# MD.net
KiCad netlist of a schematic drawn in EAGLE
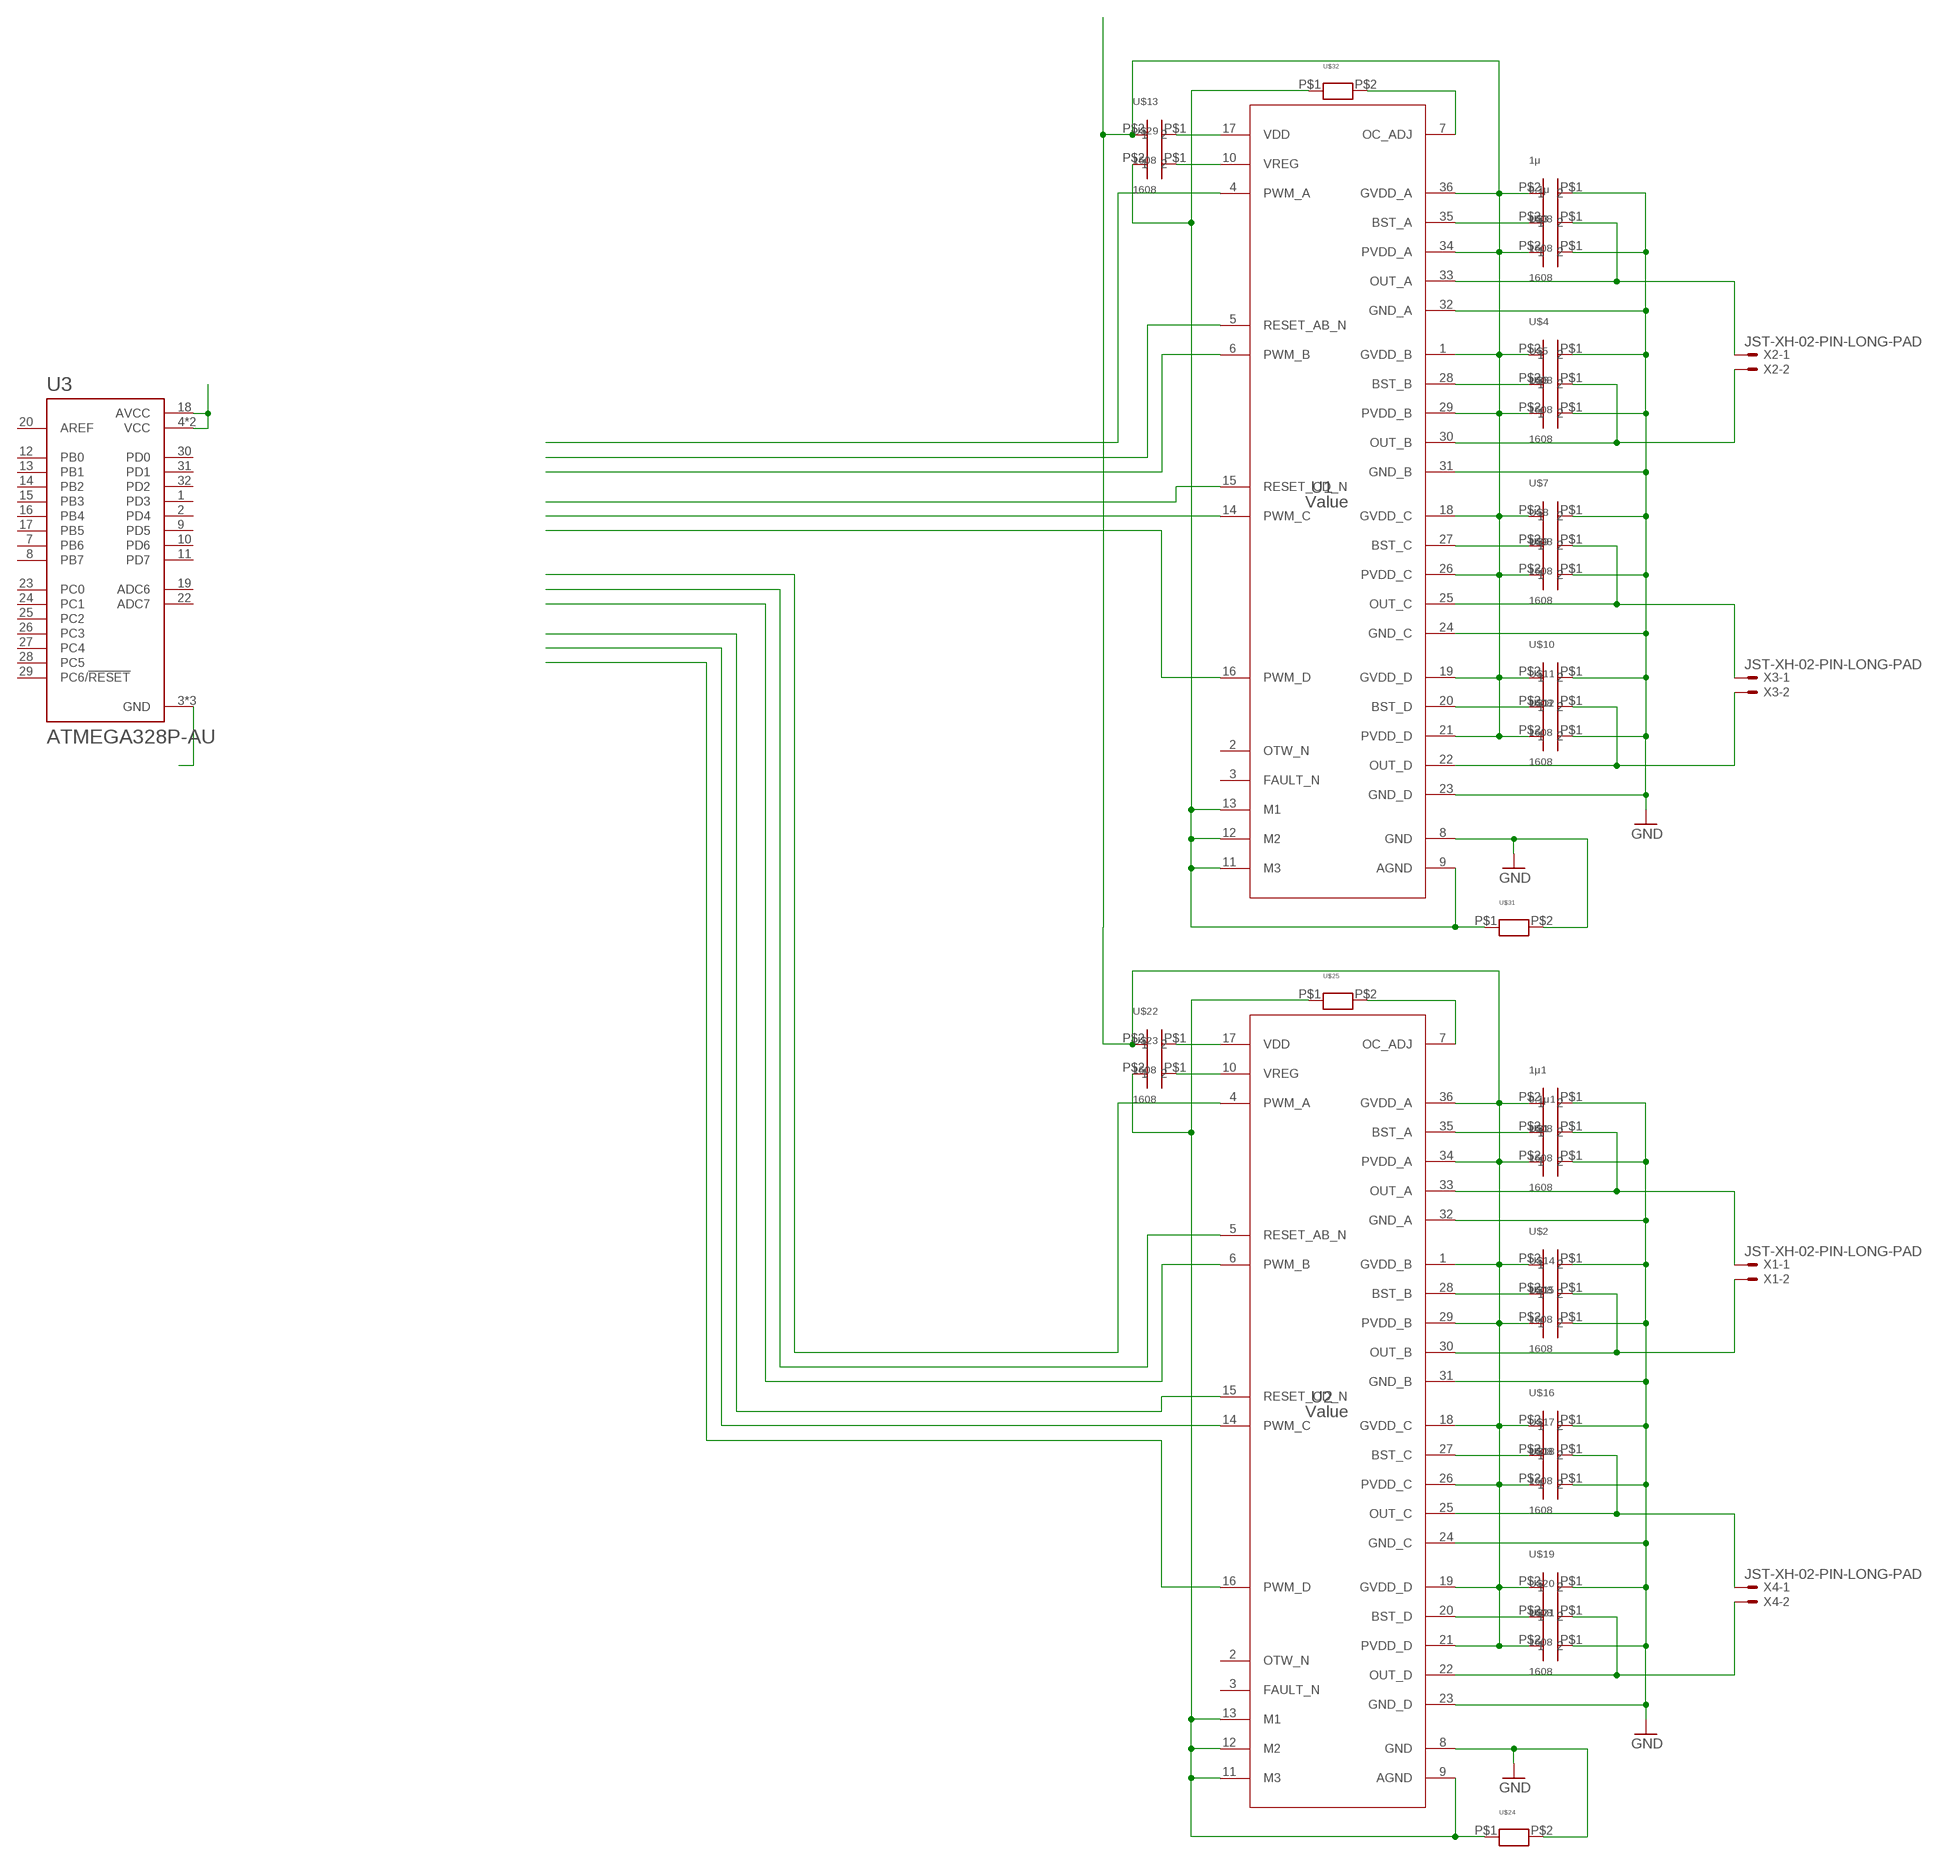
[diagram p0: schematic, sheet 1]

(export (version "E")
  (design (tool "Eeschema 10.0.6"))
  (components
    (comp (ref "0.1μ")
      (value "1608")
      (footprint "eagle-import:CON")
      (libsource (lib "eagle-import") (part "1608"))
    )
    (comp (ref "0.1μ1")
      (value "1608")
      (footprint "eagle-import:CON")
      (libsource (lib "eagle-import") (part "1608"))
    )
    (comp (ref "1μ")
      (value "1608")
      (footprint "eagle-import:CON")
      (libsource (lib "eagle-import") (part "1608"))
    )
    (comp (ref "1μ1")
      (value "1608")
      (footprint "eagle-import:CON")
      (libsource (lib "eagle-import") (part "1608"))
    )
    (comp (ref "U$1")
      (value "1608")
      (footprint "eagle-import:CON")
      (libsource (lib "eagle-import") (part "1608"))
    )
    (comp (ref "U$2")
      (value "1608")
      (footprint "eagle-import:CON")
      (libsource (lib "eagle-import") (part "1608"))
    )
    (comp (ref "U$3")
      (value "1608")
      (footprint "eagle-import:CON")
      (libsource (lib "eagle-import") (part "1608"))
    )
    (comp (ref "U$4")
      (value "1608")
      (footprint "eagle-import:CON")
      (libsource (lib "eagle-import") (part "1608"))
    )
    (comp (ref "U$5")
      (value "1608")
      (footprint "eagle-import:CON")
      (libsource (lib "eagle-import") (part "1608"))
    )
    (comp (ref "U$6")
      (value "1608")
      (footprint "eagle-import:CON")
      (libsource (lib "eagle-import") (part "1608"))
    )
    (comp (ref "U$7")
      (value "1608")
      (footprint "eagle-import:CON")
      (libsource (lib "eagle-import") (part "1608"))
    )
    (comp (ref "U$8")
      (value "1608")
      (footprint "eagle-import:CON")
      (libsource (lib "eagle-import") (part "1608"))
    )
    (comp (ref "U$9")
      (value "1608")
      (footprint "eagle-import:CON")
      (libsource (lib "eagle-import") (part "1608"))
    )
    (comp (ref "U$10")
      (value "1608")
      (footprint "eagle-import:CON")
      (libsource (lib "eagle-import") (part "1608"))
    )
    (comp (ref "U$11")
      (value "1608")
      (footprint "eagle-import:CON")
      (libsource (lib "eagle-import") (part "1608"))
    )
    (comp (ref "U$12")
      (value "1608")
      (footprint "eagle-import:CON")
      (libsource (lib "eagle-import") (part "1608"))
    )
    (comp (ref "U$13")
      (value "1608")
      (footprint "eagle-import:CON")
      (libsource (lib "eagle-import") (part "1608"))
    )
    (comp (ref "U$14")
      (value "1608")
      (footprint "eagle-import:CON")
      (libsource (lib "eagle-import") (part "1608"))
    )
    (comp (ref "U$15")
      (value "1608")
      (footprint "eagle-import:CON")
      (libsource (lib "eagle-import") (part "1608"))
    )
    (comp (ref "U$16")
      (value "1608")
      (footprint "eagle-import:CON")
      (libsource (lib "eagle-import") (part "1608"))
    )
    (comp (ref "U$17")
      (value "1608")
      (footprint "eagle-import:CON")
      (libsource (lib "eagle-import") (part "1608"))
    )
    (comp (ref "U$18")
      (value "1608")
      (footprint "eagle-import:CON")
      (libsource (lib "eagle-import") (part "1608"))
    )
    (comp (ref "U$19")
      (value "1608")
      (footprint "eagle-import:CON")
      (libsource (lib "eagle-import") (part "1608"))
    )
    (comp (ref "U$20")
      (value "1608")
      (footprint "eagle-import:CON")
      (libsource (lib "eagle-import") (part "1608"))
    )
    (comp (ref "U$21")
      (value "1608")
      (footprint "eagle-import:CON")
      (libsource (lib "eagle-import") (part "1608"))
    )
    (comp (ref "U$22")
      (value "1608")
      (footprint "eagle-import:CON")
      (libsource (lib "eagle-import") (part "1608"))
    )
    (comp (ref "U$23")
      (value "1608")
      (footprint "eagle-import:CON")
      (libsource (lib "eagle-import") (part "1608"))
    )
    (comp (ref "U$24")
      (value "R")
      (footprint "eagle-import:1608")
      (libsource (lib "eagle-import") (part "R"))
    )
    (comp (ref "U$25")
      (value "R")
      (footprint "eagle-import:1608")
      (libsource (lib "eagle-import") (part "R"))
    )
    (comp (ref "U$29")
      (value "1608")
      (footprint "eagle-import:CON")
      (libsource (lib "eagle-import") (part "1608"))
    )
    (comp (ref "U$31")
      (value "R")
      (footprint "eagle-import:1608")
      (libsource (lib "eagle-import") (part "R"))
    )
    (comp (ref "U$32")
      (value "R")
      (footprint "eagle-import:1608")
      (libsource (lib "eagle-import") (part "R"))
    )
    (comp (ref "U1")
      (value "Value")
      (footprint "eagle-import:DKD0036A")
      (fields
        (field (name "ALTERNATEPARTNUMBER") "DRV8432DKD")
        (field (name "MANUFACTURER") "Texas Instruments")
        (field (name "PARTNUMBER") "DRV8432DKDR")
      )
      (libsource (lib "eagle-import") (part "DRV8432DKDR"))
    )
    (comp (ref "U2")
      (value "Value")
      (footprint "eagle-import:DKD0036A")
      (fields
        (field (name "ALTERNATEPARTNUMBER") "DRV8432DKD")
        (field (name "MANUFACTURER") "Texas Instruments")
        (field (name "PARTNUMBER") "DRV8432DKDR")
      )
      (libsource (lib "eagle-import") (part "DRV8432DKDR"))
    )
    (comp (ref "U3")
      (value "ATMEGA328P-AU")
      (footprint "eagle-import:QFP80P900X900X120-32N")
      (fields (field (name "MF") "Microchip Technology"))
      (libsource (lib "eagle-import") (part "ATMEGA328P-AU"))
    )
    (comp (ref "X1")
      (value "JST-XH-02-PIN-LONG-PAD")
      (footprint "eagle-import:JST-XH-02-PACKAGE-LONG-PAD")
      (libsource (lib "eagle-import") (part "JST-XH-02-PIN-LONG-PAD"))
    )
    (comp (ref "X2")
      (value "JST-XH-02-PIN-LONG-PAD")
      (footprint "eagle-import:JST-XH-02-PACKAGE-LONG-PAD")
      (libsource (lib "eagle-import") (part "JST-XH-02-PIN-LONG-PAD"))
    )
    (comp (ref "X3")
      (value "JST-XH-02-PIN-LONG-PAD")
      (footprint "eagle-import:JST-XH-02-PACKAGE-LONG-PAD")
      (libsource (lib "eagle-import") (part "JST-XH-02-PIN-LONG-PAD"))
    )
    (comp (ref "X4")
      (value "JST-XH-02-PIN-LONG-PAD")
      (footprint "eagle-import:JST-XH-02-PACKAGE-LONG-PAD")
      (libsource (lib "eagle-import") (part "JST-XH-02-PIN-LONG-PAD"))
    )
  )
  (nets
    (net (code "1") (name "GND") (class "Default")
      (node (ref "1μ") (pin "P$1") (pinfunction "1_P$1") (pintype "bidirectional"))
      (node (ref "1μ1") (pin "P$1") (pinfunction "1_P$1") (pintype "bidirectional"))
      (node (ref "U$1") (pin "P$1") (pinfunction "1_P$1") (pintype "bidirectional"))
      (node (ref "U$10") (pin "P$1") (pinfunction "1_P$1") (pintype "bidirectional"))
      (node (ref "U$12") (pin "P$1") (pinfunction "1_P$1") (pintype "bidirectional"))
      (node (ref "U$15") (pin "P$1") (pinfunction "1_P$1") (pintype "bidirectional"))
      (node (ref "U$16") (pin "P$1") (pinfunction "1_P$1") (pintype "bidirectional"))
      (node (ref "U$18") (pin "P$1") (pinfunction "1_P$1") (pintype "bidirectional"))
      (node (ref "U$19") (pin "P$1") (pinfunction "1_P$1") (pintype "bidirectional"))
      (node (ref "U$2") (pin "P$1") (pinfunction "1_P$1") (pintype "bidirectional"))
      (node (ref "U$21") (pin "P$1") (pinfunction "1_P$1") (pintype "bidirectional"))
      (node (ref "U$24") (pin "P$2") (pinfunction "P$2_P$2") (pintype "bidirectional"))
      (node (ref "U$3") (pin "P$1") (pinfunction "1_P$1") (pintype "bidirectional"))
      (node (ref "U$31") (pin "P$2") (pinfunction "P$2_P$2") (pintype "bidirectional"))
      (node (ref "U$4") (pin "P$1") (pinfunction "1_P$1") (pintype "bidirectional"))
      (node (ref "U$6") (pin "P$1") (pinfunction "1_P$1") (pintype "bidirectional"))
      (node (ref "U$7") (pin "P$1") (pinfunction "1_P$1") (pintype "bidirectional"))
      (node (ref "U$9") (pin "P$1") (pinfunction "1_P$1") (pintype "bidirectional"))
      (node (ref "U1") (pin "23") (pinfunction "GND_D_23") (pintype "power_in"))
      (node (ref "U1") (pin "24") (pinfunction "GND_C_24") (pintype "power_in"))
      (node (ref "U1") (pin "31") (pinfunction "GND_B_31") (pintype "power_in"))
      (node (ref "U1") (pin "32") (pinfunction "GND_A_32") (pintype "power_in"))
      (node (ref "U1") (pin "8") (pinfunction "GND_8") (pintype "power_in"))
      (node (ref "U2") (pin "23") (pinfunction "GND_D_23") (pintype "power_in"))
      (node (ref "U2") (pin "24") (pinfunction "GND_C_24") (pintype "power_in"))
      (node (ref "U2") (pin "31") (pinfunction "GND_B_31") (pintype "power_in"))
      (node (ref "U2") (pin "32") (pinfunction "GND_A_32") (pintype "power_in"))
      (node (ref "U2") (pin "8") (pinfunction "GND_8") (pintype "power_in"))
    )
    (net (code "2") (name "Net-(0.1μ-1)") (class "Default")
      (node (ref "0.1μ") (pin "P$1") (pinfunction "1_P$1") (pintype "bidirectional"))
      (node (ref "U1") (pin "33") (pinfunction "OUT_A_33") (pintype "tri_state"))
      (node (ref "X2") (pin "1") (pinfunction "S_1") (pintype "passive"))
    )
    (net (code "3") (name "Net-(0.1μ-2)") (class "Default")
      (node (ref "0.1μ") (pin "P$2") (pinfunction "2_P$2") (pintype "bidirectional"))
      (node (ref "U1") (pin "35") (pinfunction "BST_A_35") (pintype "power_in"))
    )
    (net (code "4") (name "Net-(0.1μ1-1)") (class "Default")
      (node (ref "0.1μ1") (pin "P$1") (pinfunction "1_P$1") (pintype "bidirectional"))
      (node (ref "U2") (pin "33") (pinfunction "OUT_A_33") (pintype "tri_state"))
      (node (ref "X1") (pin "1") (pinfunction "S_1") (pintype "passive"))
    )
    (net (code "5") (name "Net-(0.1μ1-2)") (class "Default")
      (node (ref "0.1μ1") (pin "P$2") (pinfunction "2_P$2") (pintype "bidirectional"))
      (node (ref "U2") (pin "35") (pinfunction "BST_A_35") (pintype "power_in"))
    )
    (net (code "6") (name "Net-(1μ-2)") (class "Default")
      (node (ref "1μ") (pin "P$2") (pinfunction "2_P$2") (pintype "bidirectional"))
      (node (ref "1μ1") (pin "P$2") (pinfunction "2_P$2") (pintype "bidirectional"))
      (node (ref "U$1") (pin "P$2") (pinfunction "2_P$2") (pintype "bidirectional"))
      (node (ref "U$10") (pin "P$2") (pinfunction "2_P$2") (pintype "bidirectional"))
      (node (ref "U$12") (pin "P$2") (pinfunction "2_P$2") (pintype "bidirectional"))
      (node (ref "U$13") (pin "P$2") (pinfunction "2_P$2") (pintype "bidirectional"))
      (node (ref "U$15") (pin "P$2") (pinfunction "2_P$2") (pintype "bidirectional"))
      (node (ref "U$16") (pin "P$2") (pinfunction "2_P$2") (pintype "bidirectional"))
      (node (ref "U$18") (pin "P$2") (pinfunction "2_P$2") (pintype "bidirectional"))
      (node (ref "U$19") (pin "P$2") (pinfunction "2_P$2") (pintype "bidirectional"))
      (node (ref "U$2") (pin "P$2") (pinfunction "2_P$2") (pintype "bidirectional"))
      (node (ref "U$21") (pin "P$2") (pinfunction "2_P$2") (pintype "bidirectional"))
      (node (ref "U$22") (pin "P$2") (pinfunction "2_P$2") (pintype "bidirectional"))
      (node (ref "U$3") (pin "P$2") (pinfunction "2_P$2") (pintype "bidirectional"))
      (node (ref "U$4") (pin "P$2") (pinfunction "2_P$2") (pintype "bidirectional"))
      (node (ref "U$6") (pin "P$2") (pinfunction "2_P$2") (pintype "bidirectional"))
      (node (ref "U$7") (pin "P$2") (pinfunction "2_P$2") (pintype "bidirectional"))
      (node (ref "U$9") (pin "P$2") (pinfunction "2_P$2") (pintype "bidirectional"))
      (node (ref "U1") (pin "1") (pinfunction "GVDD_B_1") (pintype "power_in"))
      (node (ref "U1") (pin "18") (pinfunction "GVDD_C_18") (pintype "power_in"))
      (node (ref "U1") (pin "19") (pinfunction "GVDD_D_19") (pintype "power_in"))
      (node (ref "U1") (pin "21") (pinfunction "PVDD_D_21") (pintype "power_in"))
      (node (ref "U1") (pin "26") (pinfunction "PVDD_C_26") (pintype "power_in"))
      (node (ref "U1") (pin "29") (pinfunction "PVDD_B_29") (pintype "power_in"))
      (node (ref "U1") (pin "34") (pinfunction "PVDD_A_34") (pintype "power_in"))
      (node (ref "U1") (pin "36") (pinfunction "GVDD_A_36") (pintype "power_in"))
      (node (ref "U2") (pin "1") (pinfunction "GVDD_B_1") (pintype "power_in"))
      (node (ref "U2") (pin "18") (pinfunction "GVDD_C_18") (pintype "power_in"))
      (node (ref "U2") (pin "19") (pinfunction "GVDD_D_19") (pintype "power_in"))
      (node (ref "U2") (pin "21") (pinfunction "PVDD_D_21") (pintype "power_in"))
      (node (ref "U2") (pin "26") (pinfunction "PVDD_C_26") (pintype "power_in"))
      (node (ref "U2") (pin "29") (pinfunction "PVDD_B_29") (pintype "power_in"))
      (node (ref "U2") (pin "34") (pinfunction "PVDD_A_34") (pintype "power_in"))
      (node (ref "U2") (pin "36") (pinfunction "GVDD_A_36") (pintype "power_in"))
    )
    (net (code "7") (name "Net-(U$5-1)") (class "Default")
      (node (ref "U$5") (pin "P$1") (pinfunction "1_P$1") (pintype "bidirectional"))
      (node (ref "U1") (pin "30") (pinfunction "OUT_B_30") (pintype "tri_state"))
      (node (ref "X2") (pin "2") (pinfunction "S_2") (pintype "passive"))
    )
    (net (code "8") (name "Net-(U$5-2)") (class "Default")
      (node (ref "U$5") (pin "P$2") (pinfunction "2_P$2") (pintype "bidirectional"))
      (node (ref "U1") (pin "28") (pinfunction "BST_B_28") (pintype "power_in"))
    )
    (net (code "9") (name "Net-(U$8-1)") (class "Default")
      (node (ref "U$8") (pin "P$1") (pinfunction "1_P$1") (pintype "bidirectional"))
      (node (ref "U1") (pin "25") (pinfunction "OUT_C_25") (pintype "tri_state"))
      (node (ref "X3") (pin "1") (pinfunction "S_1") (pintype "passive"))
    )
    (net (code "10") (name "Net-(U$8-2)") (class "Default")
      (node (ref "U$8") (pin "P$2") (pinfunction "2_P$2") (pintype "bidirectional"))
      (node (ref "U1") (pin "27") (pinfunction "BST_C_27") (pintype "power_in"))
    )
    (net (code "11") (name "Net-(U$11-1)") (class "Default")
      (node (ref "U$11") (pin "P$1") (pinfunction "1_P$1") (pintype "bidirectional"))
      (node (ref "U1") (pin "22") (pinfunction "OUT_D_22") (pintype "tri_state"))
      (node (ref "X3") (pin "2") (pinfunction "S_2") (pintype "passive"))
    )
    (net (code "12") (name "Net-(U$11-2)") (class "Default")
      (node (ref "U$11") (pin "P$2") (pinfunction "2_P$2") (pintype "bidirectional"))
      (node (ref "U1") (pin "20") (pinfunction "BST_D_20") (pintype "power_in"))
    )
    (net (code "13") (name "Net-(U$13-1)") (class "Default")
      (node (ref "U$13") (pin "P$1") (pinfunction "1_P$1") (pintype "bidirectional"))
      (node (ref "U1") (pin "17") (pinfunction "VDD_17") (pintype "power_in"))
    )
    (net (code "14") (name "Net-(U$14-1)") (class "Default")
      (node (ref "U$14") (pin "P$1") (pinfunction "1_P$1") (pintype "bidirectional"))
      (node (ref "U2") (pin "30") (pinfunction "OUT_B_30") (pintype "tri_state"))
      (node (ref "X1") (pin "2") (pinfunction "S_2") (pintype "passive"))
    )
    (net (code "15") (name "Net-(U$14-2)") (class "Default")
      (node (ref "U$14") (pin "P$2") (pinfunction "2_P$2") (pintype "bidirectional"))
      (node (ref "U2") (pin "28") (pinfunction "BST_B_28") (pintype "power_in"))
    )
    (net (code "16") (name "Net-(U$17-1)") (class "Default")
      (node (ref "U$17") (pin "P$1") (pinfunction "1_P$1") (pintype "bidirectional"))
      (node (ref "U2") (pin "25") (pinfunction "OUT_C_25") (pintype "tri_state"))
      (node (ref "X4") (pin "1") (pinfunction "S_1") (pintype "passive"))
    )
    (net (code "17") (name "Net-(U$17-2)") (class "Default")
      (node (ref "U$17") (pin "P$2") (pinfunction "2_P$2") (pintype "bidirectional"))
      (node (ref "U2") (pin "27") (pinfunction "BST_C_27") (pintype "power_in"))
    )
    (net (code "18") (name "Net-(U$20-1)") (class "Default")
      (node (ref "U$20") (pin "P$1") (pinfunction "1_P$1") (pintype "bidirectional"))
      (node (ref "U2") (pin "22") (pinfunction "OUT_D_22") (pintype "tri_state"))
      (node (ref "X4") (pin "2") (pinfunction "S_2") (pintype "passive"))
    )
    (net (code "19") (name "Net-(U$20-2)") (class "Default")
      (node (ref "U$20") (pin "P$2") (pinfunction "2_P$2") (pintype "bidirectional"))
      (node (ref "U2") (pin "20") (pinfunction "BST_D_20") (pintype "power_in"))
    )
    (net (code "20") (name "Net-(U$22-1)") (class "Default")
      (node (ref "U$22") (pin "P$1") (pinfunction "1_P$1") (pintype "bidirectional"))
      (node (ref "U2") (pin "17") (pinfunction "VDD_17") (pintype "power_in"))
    )
    (net (code "21") (name "Net-(U$23-1)") (class "Default")
      (node (ref "U$23") (pin "P$1") (pinfunction "1_P$1") (pintype "bidirectional"))
      (node (ref "U2") (pin "10") (pinfunction "VREG_10") (pintype "power_in"))
    )
    (net (code "22") (name "Net-(U$23-2)") (class "Default")
      (node (ref "U$23") (pin "P$2") (pinfunction "2_P$2") (pintype "bidirectional"))
      (node (ref "U$24") (pin "P$1") (pinfunction "P$1_P$1") (pintype "bidirectional"))
      (node (ref "U$25") (pin "P$1") (pinfunction "P$1_P$1") (pintype "bidirectional"))
      (node (ref "U2") (pin "11") (pinfunction "M3_11") (pintype "power_in"))
      (node (ref "U2") (pin "12") (pinfunction "M2_12") (pintype "input"))
      (node (ref "U2") (pin "13") (pinfunction "M1_13") (pintype "input"))
      (node (ref "U2") (pin "9") (pinfunction "AGND_9") (pintype "power_in"))
    )
    (net (code "23") (name "Net-(U$29-1)") (class "Default")
      (node (ref "U$29") (pin "P$1") (pinfunction "1_P$1") (pintype "bidirectional"))
      (node (ref "U1") (pin "10") (pinfunction "VREG_10") (pintype "power_in"))
    )
    (net (code "24") (name "Net-(U$29-2)") (class "Default")
      (node (ref "U$29") (pin "P$2") (pinfunction "2_P$2") (pintype "bidirectional"))
      (node (ref "U$31") (pin "P$1") (pinfunction "P$1_P$1") (pintype "bidirectional"))
      (node (ref "U$32") (pin "P$1") (pinfunction "P$1_P$1") (pintype "bidirectional"))
      (node (ref "U1") (pin "11") (pinfunction "M3_11") (pintype "power_in"))
      (node (ref "U1") (pin "12") (pinfunction "M2_12") (pintype "input"))
      (node (ref "U1") (pin "13") (pinfunction "M1_13") (pintype "input"))
      (node (ref "U1") (pin "9") (pinfunction "AGND_9") (pintype "power_in"))
    )
    (net (code "25") (name "Net-(U1-OC_ADJ)") (class "Default")
      (node (ref "U$32") (pin "P$2") (pinfunction "P$2_P$2") (pintype "bidirectional"))
      (node (ref "U1") (pin "7") (pinfunction "OC_ADJ_7") (pintype "passive"))
    )
    (net (code "26") (name "Net-(U2-OC_ADJ)") (class "Default")
      (node (ref "U$25") (pin "P$2") (pinfunction "P$2_P$2") (pintype "bidirectional"))
      (node (ref "U2") (pin "7") (pinfunction "OC_ADJ_7") (pintype "passive"))
    )
    (net (code "27") (name "Net-(U3-AVCC)") (class "Default")
      (node (ref "U3") (pin "18") (pinfunction "AVCC_18") (pintype "power_in"))
      (node (ref "U3") (pin "4") (pinfunction "VCC_4") (pintype "power_in"))
      (node (ref "U3") (pin "6") (pinfunction "VCC_6") (pintype "power_in"))
    )
    (net (code "28") (name "Net-(U3-GND-Pad21)") (class "Default")
      (node (ref "U3") (pin "21") (pinfunction "GND_21") (pintype "power_in"))
      (node (ref "U3") (pin "3") (pinfunction "GND_3") (pintype "power_in"))
      (node (ref "U3") (pin "5") (pinfunction "GND_5") (pintype "power_in"))
    )
    (net (code "29") (name "unconnected-(U1-FAULT_N-Pad3)") (class "Default")
      (node (ref "U1") (pin "3") (pinfunction "FAULT_N_3") (pintype "open_collector"))
    )
    (net (code "30") (name "unconnected-(U1-OTW_N-Pad2)") (class "Default")
      (node (ref "U1") (pin "2") (pinfunction "OTW_N_2") (pintype "open_collector"))
    )
    (net (code "31") (name "unconnected-(U1-PWM_A-Pad4)") (class "Default")
      (node (ref "U1") (pin "4") (pinfunction "PWM_A_4") (pintype "input"))
    )
    (net (code "32") (name "unconnected-(U1-PWM_B-Pad6)") (class "Default")
      (node (ref "U1") (pin "6") (pinfunction "PWM_B_6") (pintype "input"))
    )
    (net (code "33") (name "unconnected-(U1-PWM_C-Pad14)") (class "Default")
      (node (ref "U1") (pin "14") (pinfunction "PWM_C_14") (pintype "input"))
    )
    (net (code "34") (name "unconnected-(U1-PWM_D-Pad16)") (class "Default")
      (node (ref "U1") (pin "16") (pinfunction "PWM_D_16") (pintype "input"))
    )
    (net (code "35") (name "unconnected-(U1-RESET_AB_N-Pad5)") (class "Default")
      (node (ref "U1") (pin "5") (pinfunction "RESET_AB_N_5") (pintype "input"))
    )
    (net (code "36") (name "unconnected-(U1-RESET_CD_N-Pad15)") (class "Default")
      (node (ref "U1") (pin "15") (pinfunction "RESET_CD_N_15") (pintype "input"))
    )
    (net (code "37") (name "unconnected-(U2-FAULT_N-Pad3)") (class "Default")
      (node (ref "U2") (pin "3") (pinfunction "FAULT_N_3") (pintype "open_collector"))
    )
    (net (code "38") (name "unconnected-(U2-OTW_N-Pad2)") (class "Default")
      (node (ref "U2") (pin "2") (pinfunction "OTW_N_2") (pintype "open_collector"))
    )
    (net (code "39") (name "unconnected-(U2-PWM_A-Pad4)") (class "Default")
      (node (ref "U2") (pin "4") (pinfunction "PWM_A_4") (pintype "input"))
    )
    (net (code "40") (name "unconnected-(U2-PWM_B-Pad6)") (class "Default")
      (node (ref "U2") (pin "6") (pinfunction "PWM_B_6") (pintype "input"))
    )
    (net (code "41") (name "unconnected-(U2-PWM_C-Pad14)") (class "Default")
      (node (ref "U2") (pin "14") (pinfunction "PWM_C_14") (pintype "input"))
    )
    (net (code "42") (name "unconnected-(U2-PWM_D-Pad16)") (class "Default")
      (node (ref "U2") (pin "16") (pinfunction "PWM_D_16") (pintype "input"))
    )
    (net (code "43") (name "unconnected-(U2-RESET_AB_N-Pad5)") (class "Default")
      (node (ref "U2") (pin "5") (pinfunction "RESET_AB_N_5") (pintype "input"))
    )
    (net (code "44") (name "unconnected-(U2-RESET_CD_N-Pad15)") (class "Default")
      (node (ref "U2") (pin "15") (pinfunction "RESET_CD_N_15") (pintype "input"))
    )
    (net (code "45") (name "unconnected-(U3-ADC6-Pad19)") (class "Default")
      (node (ref "U3") (pin "19") (pinfunction "ADC6_19") (pintype "bidirectional"))
    )
    (net (code "46") (name "unconnected-(U3-ADC7-Pad22)") (class "Default")
      (node (ref "U3") (pin "22") (pinfunction "ADC7_22") (pintype "bidirectional"))
    )
    (net (code "47") (name "unconnected-(U3-AREF-Pad20)") (class "Default")
      (node (ref "U3") (pin "20") (pinfunction "AREF_20") (pintype "input"))
    )
    (net (code "48") (name "unconnected-(U3-PB0-Pad12)") (class "Default")
      (node (ref "U3") (pin "12") (pinfunction "PB0_12") (pintype "bidirectional"))
    )
    (net (code "49") (name "unconnected-(U3-PB1-Pad13)") (class "Default")
      (node (ref "U3") (pin "13") (pinfunction "PB1_13") (pintype "bidirectional"))
    )
    (net (code "50") (name "unconnected-(U3-PB2-Pad14)") (class "Default")
      (node (ref "U3") (pin "14") (pinfunction "PB2_14") (pintype "bidirectional"))
    )
    (net (code "51") (name "unconnected-(U3-PB3-Pad15)") (class "Default")
      (node (ref "U3") (pin "15") (pinfunction "PB3_15") (pintype "bidirectional"))
    )
    (net (code "52") (name "unconnected-(U3-PB4-Pad16)") (class "Default")
      (node (ref "U3") (pin "16") (pinfunction "PB4_16") (pintype "bidirectional"))
    )
    (net (code "53") (name "unconnected-(U3-PB5-Pad17)") (class "Default")
      (node (ref "U3") (pin "17") (pinfunction "PB5_17") (pintype "bidirectional"))
    )
    (net (code "54") (name "unconnected-(U3-PB6-Pad7)") (class "Default")
      (node (ref "U3") (pin "7") (pinfunction "PB6_7") (pintype "bidirectional"))
    )
    (net (code "55") (name "unconnected-(U3-PB7-Pad8)") (class "Default")
      (node (ref "U3") (pin "8") (pinfunction "PB7_8") (pintype "bidirectional"))
    )
    (net (code "56") (name "unconnected-(U3-PC0-Pad23)") (class "Default")
      (node (ref "U3") (pin "23") (pinfunction "PC0_23") (pintype "bidirectional"))
    )
    (net (code "57") (name "unconnected-(U3-PC1-Pad24)") (class "Default")
      (node (ref "U3") (pin "24") (pinfunction "PC1_24") (pintype "bidirectional"))
    )
    (net (code "58") (name "unconnected-(U3-PC2-Pad25)") (class "Default")
      (node (ref "U3") (pin "25") (pinfunction "PC2_25") (pintype "bidirectional"))
    )
    (net (code "59") (name "unconnected-(U3-PC3-Pad26)") (class "Default")
      (node (ref "U3") (pin "26") (pinfunction "PC3_26") (pintype "bidirectional"))
    )
    (net (code "60") (name "unconnected-(U3-PC4-Pad27)") (class "Default")
      (node (ref "U3") (pin "27") (pinfunction "PC4_27") (pintype "bidirectional"))
    )
    (net (code "61") (name "unconnected-(U3-PC5-Pad28)") (class "Default")
      (node (ref "U3") (pin "28") (pinfunction "PC5_28") (pintype "bidirectional"))
    )
    (net (code "62") (name "unconnected-(U3-PC6{slash}~{RESET}-Pad29)") (class "Default")
      (node (ref "U3") (pin "29") (pinfunction "PC6/~{RESET}_29") (pintype "bidirectional"))
    )
    (net (code "63") (name "unconnected-(U3-PD0-Pad30)") (class "Default")
      (node (ref "U3") (pin "30") (pinfunction "PD0_30") (pintype "bidirectional"))
    )
    (net (code "64") (name "unconnected-(U3-PD1-Pad31)") (class "Default")
      (node (ref "U3") (pin "31") (pinfunction "PD1_31") (pintype "bidirectional"))
    )
    (net (code "65") (name "unconnected-(U3-PD2-Pad32)") (class "Default")
      (node (ref "U3") (pin "32") (pinfunction "PD2_32") (pintype "bidirectional"))
    )
    (net (code "66") (name "unconnected-(U3-PD3-Pad1)") (class "Default")
      (node (ref "U3") (pin "1") (pinfunction "PD3_1") (pintype "bidirectional"))
    )
    (net (code "67") (name "unconnected-(U3-PD4-Pad2)") (class "Default")
      (node (ref "U3") (pin "2") (pinfunction "PD4_2") (pintype "bidirectional"))
    )
    (net (code "68") (name "unconnected-(U3-PD5-Pad9)") (class "Default")
      (node (ref "U3") (pin "9") (pinfunction "PD5_9") (pintype "bidirectional"))
    )
    (net (code "69") (name "unconnected-(U3-PD6-Pad10)") (class "Default")
      (node (ref "U3") (pin "10") (pinfunction "PD6_10") (pintype "bidirectional"))
    )
    (net (code "70") (name "unconnected-(U3-PD7-Pad11)") (class "Default")
      (node (ref "U3") (pin "11") (pinfunction "PD7_11") (pintype "bidirectional"))
    )
  )
)
